# sematik.net
KiCad netlist of a schematic drawn in Altium Designer
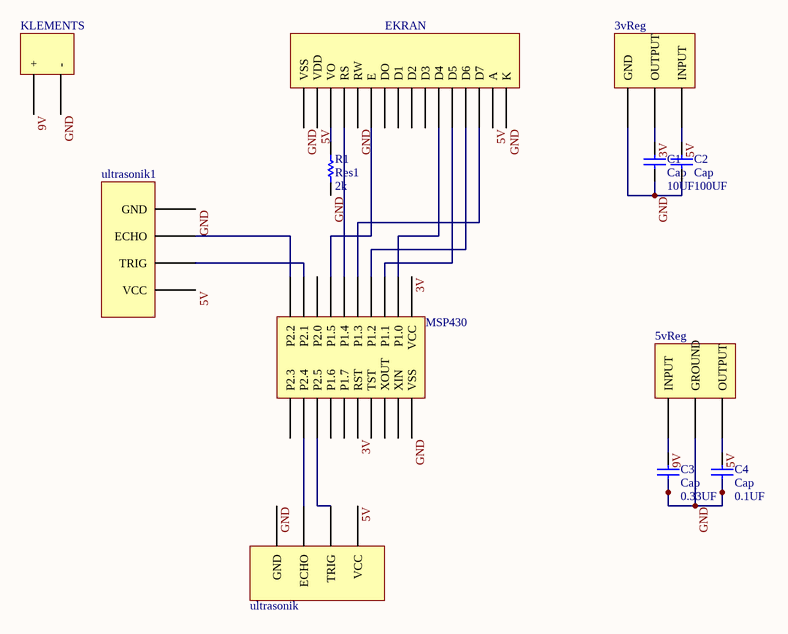
[diagram p0: sematik.SchDoc]

(export (version "E")
  (design (tool "Eeschema 10.0.6"))
  (components
    (comp (ref "3vReg")
      (value "LM1117")
      (footprint "3v3regulatorum_")
      (libsource (lib "kutuphane_sematik") (part "LM1117"))
    )
    (comp (ref "5vReg")
      (value "LM7805")
      (footprint "5vregulatorum_")
      (libsource (lib "kutuphane_sematik") (part "LM7805"))
    )
    (comp (ref "C1")
      (value "Cap")
      (footprint "RAD-0.3")
      (description "Capacitor")
      (fields (field (name "ALTIUM_VALUE") "10UF") (field (name "PUBLISHER") "Altium Limited"))
      (libsource (lib "Miscellaneous Devices") (part "Cap"))
    )
    (comp (ref "C2")
      (value "Cap")
      (footprint "RAD-0.3")
      (description "Capacitor")
      (fields (field (name "ALTIUM_VALUE") "100UF") (field (name "PUBLISHER") "Altium Limited"))
      (libsource (lib "Miscellaneous Devices") (part "Cap"))
    )
    (comp (ref "C3")
      (value "Cap")
      (footprint "RAD-0.3")
      (description "Capacitor")
      (fields (field (name "ALTIUM_VALUE") "0.33UF") (field (name "PUBLISHER") "Altium Limited"))
      (libsource (lib "Miscellaneous Devices") (part "Cap"))
    )
    (comp (ref "C4")
      (value "Cap")
      (footprint "RAD-0.3")
      (description "Capacitor")
      (fields (field (name "ALTIUM_VALUE") "0.1UF") (field (name "PUBLISHER") "Altium Limited"))
      (libsource (lib "Miscellaneous Devices") (part "Cap"))
    )
    (comp (ref "EKRAN")
      (value "EKRAN")
      (footprint "EKRAN - duplicate")
      (libsource (lib "kutuphane_sematik") (part "EKRAN"))
    )
    (comp (ref "KLEMENTS")
      (value "KLEMENTS")
      (footprint "klements")
      (libsource (lib "kutuphane_sematik") (part "KLEMENTS"))
    )
    (comp (ref "MSP430")
      (value "MSP430")
      (footprint "msp430")
      (libsource (lib "kutuphane_sematik") (part "MSP430"))
    )
    (comp (ref "R1")
      (value "Res1")
      (footprint "AXIAL-0.3")
      (description "Resistor")
      (fields (field (name "ALTIUM_VALUE") "2k") (field (name "PUBLISHER") "Altium Limited"))
      (libsource (lib "Miscellaneous Devices") (part "Res1"))
    )
    (comp (ref "ultrasonik")
      (value "ultrasonik")
      (footprint "ultrasonik")
      (libsource (lib "") (part "ultrasonik_1"))
    )
    (comp (ref "ultrasonik1")
      (value "ultrasonik")
      (footprint "ultrasonik")
      (libsource (lib "kutuphane_sematik") (part "ultrasonik"))
    )
  )
  (nets
    (net (code "1") (name "/3V") (class "Default")
      (node (ref "3vReg") (pin "1") (pinfunction "OUTPUT_1") (pintype "passive"))
      (node (ref "C1") (pin "2") (pinfunction "2_2") (pintype "passive"))
      (node (ref "MSP430") (pin "1") (pinfunction "VCC_1") (pintype "passive"))
      (node (ref "MSP430") (pin "16") (pinfunction "RST_16") (pintype "passive"))
    )
    (net (code "2") (name "/5V") (class "Default")
      (node (ref "3vReg") (pin "2") (pinfunction "INPUT_2") (pintype "passive"))
      (node (ref "5vReg") (pin "3") (pinfunction "OUTPUT_3") (pintype "passive"))
      (node (ref "C2") (pin "2") (pinfunction "2_2") (pintype "passive"))
      (node (ref "C4") (pin "2") (pinfunction "2_2") (pintype "passive"))
      (node (ref "EKRAN") (pin "15") (pinfunction "A_15") (pintype "passive"))
      (node (ref "EKRAN") (pin "2") (pinfunction "VDD_2") (pintype "passive"))
      (node (ref "ultrasonik") (pin "1") (pinfunction "VCC_1") (pintype "passive"))
      (node (ref "ultrasonik1") (pin "1") (pinfunction "VCC_1") (pintype "passive"))
    )
    (net (code "3") (name "/9V") (class "Default")
      (node (ref "5vReg") (pin "1") (pinfunction "INPUT_1") (pintype "passive"))
      (node (ref "C3") (pin "2") (pinfunction "2_2") (pintype "passive"))
      (node (ref "KLEMENTS") (pin "1") (pinfunction "+_1") (pintype "passive"))
    )
    (net (code "4") (name "/GND") (class "Default")
      (node (ref "3vReg") (pin "0") (pinfunction "GND_0") (pintype "passive"))
      (node (ref "5vReg") (pin "2") (pinfunction "GROUND_2") (pintype "passive"))
      (node (ref "C1") (pin "1") (pinfunction "1_1") (pintype "passive"))
      (node (ref "C2") (pin "1") (pinfunction "1_1") (pintype "passive"))
      (node (ref "C3") (pin "1") (pinfunction "1_1") (pintype "passive"))
      (node (ref "C4") (pin "1") (pinfunction "1_1") (pintype "passive"))
      (node (ref "EKRAN") (pin "1") (pinfunction "VSS_1") (pintype "passive"))
      (node (ref "EKRAN") (pin "16") (pinfunction "K_16") (pintype "passive"))
      (node (ref "EKRAN") (pin "5") (pinfunction "RW_5") (pintype "passive"))
      (node (ref "KLEMENTS") (pin "2") (pinfunction "-_2") (pintype "passive"))
      (node (ref "MSP430") (pin "20") (pinfunction "VSS_20") (pintype "passive"))
      (node (ref "R1") (pin "1") (pinfunction "1_1") (pintype "passive"))
      (node (ref "ultrasonik") (pin "4") (pinfunction "GND_4") (pintype "passive"))
      (node (ref "ultrasonik1") (pin "4") (pinfunction "GND_4") (pintype "passive"))
    )
    (net (code "5") (name "Net-(EKRAN-D4)") (class "Default")
      (node (ref "EKRAN") (pin "11") (pinfunction "D4_11") (pintype "passive"))
      (node (ref "MSP430") (pin "2") (pinfunction "P1.0_2") (pintype "passive"))
    )
    (net (code "6") (name "Net-(EKRAN-D5)") (class "Default")
      (node (ref "EKRAN") (pin "12") (pinfunction "D5_12") (pintype "passive"))
      (node (ref "MSP430") (pin "3") (pinfunction "P1.1_3") (pintype "passive"))
    )
    (net (code "7") (name "Net-(EKRAN-D6)") (class "Default")
      (node (ref "EKRAN") (pin "13") (pinfunction "D6_13") (pintype "passive"))
      (node (ref "MSP430") (pin "4") (pinfunction "P1.2_4") (pintype "passive"))
    )
    (net (code "8") (name "Net-(EKRAN-D7)") (class "Default")
      (node (ref "EKRAN") (pin "14") (pinfunction "D7_14") (pintype "passive"))
      (node (ref "MSP430") (pin "5") (pinfunction "P1.3_5") (pintype "passive"))
    )
    (net (code "9") (name "Net-(EKRAN-E)") (class "Default")
      (node (ref "EKRAN") (pin "6") (pinfunction "E_6") (pintype "passive"))
      (node (ref "MSP430") (pin "7") (pinfunction "P1.5_7") (pintype "passive"))
    )
    (net (code "10") (name "Net-(EKRAN-RS)") (class "Default")
      (node (ref "EKRAN") (pin "4") (pinfunction "RS_4") (pintype "passive"))
      (node (ref "MSP430") (pin "6") (pinfunction "P1.4_6") (pintype "passive"))
    )
    (net (code "11") (name "Net-(EKRAN-VO)") (class "Default")
      (node (ref "EKRAN") (pin "3") (pinfunction "VO_3") (pintype "passive"))
      (node (ref "R1") (pin "2") (pinfunction "2_2") (pintype "passive"))
    )
    (net (code "12") (name "Net-(MSP430-P2.1)") (class "Default")
      (node (ref "MSP430") (pin "9") (pinfunction "P2.1_9") (pintype "passive"))
      (node (ref "ultrasonik1") (pin "2") (pinfunction "TRIG_2") (pintype "passive"))
    )
    (net (code "13") (name "Net-(MSP430-P2.2)") (class "Default")
      (node (ref "MSP430") (pin "10") (pinfunction "P2.2_10") (pintype "passive"))
      (node (ref "ultrasonik1") (pin "3") (pinfunction "ECHO_3") (pintype "passive"))
    )
    (net (code "14") (name "Net-(MSP430-P2.4)") (class "Default")
      (node (ref "MSP430") (pin "12") (pinfunction "P2.4_12") (pintype "passive"))
      (node (ref "ultrasonik") (pin "3") (pinfunction "ECHO_3") (pintype "passive"))
    )
    (net (code "15") (name "Net-(MSP430-P2.5)") (class "Default")
      (node (ref "MSP430") (pin "13") (pinfunction "P2.5_13") (pintype "passive"))
      (node (ref "ultrasonik") (pin "2") (pinfunction "TRIG_2") (pintype "passive"))
    )
    (net (code "16") (name "unconnected-(EKRAN-D1-Pad8)") (class "Default")
      (node (ref "EKRAN") (pin "8") (pinfunction "D1_8") (pintype "passive"))
    )
    (net (code "17") (name "unconnected-(EKRAN-D2-Pad9)") (class "Default")
      (node (ref "EKRAN") (pin "9") (pinfunction "D2_9") (pintype "passive"))
    )
    (net (code "18") (name "unconnected-(EKRAN-D3-Pad10)") (class "Default")
      (node (ref "EKRAN") (pin "10") (pinfunction "D3_10") (pintype "passive"))
    )
    (net (code "19") (name "unconnected-(EKRAN-DO-Pad7)") (class "Default")
      (node (ref "EKRAN") (pin "7") (pinfunction "DO_7") (pintype "passive"))
    )
    (net (code "20") (name "unconnected-(MSP430-P1.6-Pad14)") (class "Default")
      (node (ref "MSP430") (pin "14") (pinfunction "P1.6_14") (pintype "passive"))
    )
    (net (code "21") (name "unconnected-(MSP430-P1.7-Pad15)") (class "Default")
      (node (ref "MSP430") (pin "15") (pinfunction "P1.7_15") (pintype "passive"))
    )
    (net (code "22") (name "unconnected-(MSP430-P2.0-Pad8)") (class "Default")
      (node (ref "MSP430") (pin "8") (pinfunction "P2.0_8") (pintype "passive"))
    )
    (net (code "23") (name "unconnected-(MSP430-P2.3-Pad11)") (class "Default")
      (node (ref "MSP430") (pin "11") (pinfunction "P2.3_11") (pintype "passive"))
    )
    (net (code "24") (name "unconnected-(MSP430-TST-Pad17)") (class "Default")
      (node (ref "MSP430") (pin "17") (pinfunction "TST_17") (pintype "passive"))
    )
    (net (code "25") (name "unconnected-(MSP430-XIN-Pad19)") (class "Default")
      (node (ref "MSP430") (pin "19") (pinfunction "XIN_19") (pintype "passive"))
    )
    (net (code "26") (name "unconnected-(MSP430-XOUT-Pad18)") (class "Default")
      (node (ref "MSP430") (pin "18") (pinfunction "XOUT_18") (pintype "passive"))
    )
  )
)
